# D-Sub_Adapter.net
KiCad netlist of a schematic drawn in EAGLE
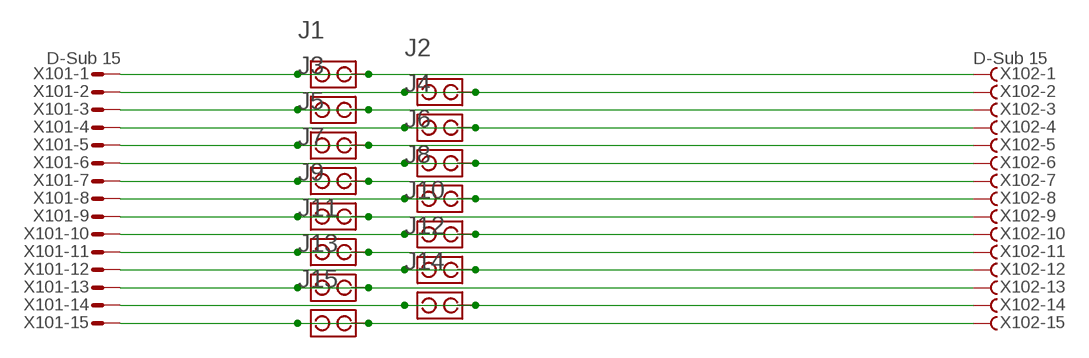
[diagram p0: schematic, sheet 1]

(export (version "E")
  (design (tool "Eeschema 10.0.6"))
  (components
    (comp (ref "J1")
      (value "JUMPER")
      (footprint "eagle-import:JUMPER")
      (libsource (lib "eagle-import") (part "JUMPER"))
    )
    (comp (ref "J2")
      (value "JUMPER")
      (footprint "eagle-import:JUMPER")
      (libsource (lib "eagle-import") (part "JUMPER"))
    )
    (comp (ref "J3")
      (value "JUMPER")
      (footprint "eagle-import:JUMPER")
      (libsource (lib "eagle-import") (part "JUMPER"))
    )
    (comp (ref "J4")
      (value "JUMPER")
      (footprint "eagle-import:JUMPER")
      (libsource (lib "eagle-import") (part "JUMPER"))
    )
    (comp (ref "J5")
      (value "JUMPER")
      (footprint "eagle-import:JUMPER")
      (libsource (lib "eagle-import") (part "JUMPER"))
    )
    (comp (ref "J6")
      (value "JUMPER")
      (footprint "eagle-import:JUMPER")
      (libsource (lib "eagle-import") (part "JUMPER"))
    )
    (comp (ref "J7")
      (value "JUMPER")
      (footprint "eagle-import:JUMPER")
      (libsource (lib "eagle-import") (part "JUMPER"))
    )
    (comp (ref "J8")
      (value "JUMPER")
      (footprint "eagle-import:JUMPER")
      (libsource (lib "eagle-import") (part "JUMPER"))
    )
    (comp (ref "J9")
      (value "JUMPER")
      (footprint "eagle-import:JUMPER")
      (libsource (lib "eagle-import") (part "JUMPER"))
    )
    (comp (ref "J10")
      (value "JUMPER")
      (footprint "eagle-import:JUMPER")
      (libsource (lib "eagle-import") (part "JUMPER"))
    )
    (comp (ref "J11")
      (value "JUMPER")
      (footprint "eagle-import:JUMPER")
      (libsource (lib "eagle-import") (part "JUMPER"))
    )
    (comp (ref "J12")
      (value "JUMPER")
      (footprint "eagle-import:JUMPER")
      (libsource (lib "eagle-import") (part "JUMPER"))
    )
    (comp (ref "J13")
      (value "JUMPER")
      (footprint "eagle-import:JUMPER")
      (libsource (lib "eagle-import") (part "JUMPER"))
    )
    (comp (ref "J14")
      (value "JUMPER")
      (footprint "eagle-import:JUMPER")
      (libsource (lib "eagle-import") (part "JUMPER"))
    )
    (comp (ref "J15")
      (value "JUMPER")
      (footprint "eagle-import:JUMPER")
      (libsource (lib "eagle-import") (part "JUMPER"))
    )
    (comp (ref "X101")
      (value "D-Sub 15")
      (footprint "eagle-import:M15HP")
      (libsource (lib "eagle-import") (part "M15?SHP"))
    )
    (comp (ref "X102")
      (value "D-Sub 15")
      (footprint "eagle-import:F15HP")
      (libsource (lib "eagle-import") (part "F15?SHP"))
    )
  )
  (nets
    (net (code "1") (name "Net-(X101A-M)") (class "Default")
      (node (ref "J1") (pin "1") (pinfunction "1_1") (pintype "bidirectional"))
      (node (ref "J1") (pin "2") (pinfunction "2_2") (pintype "bidirectional"))
      (node (ref "X101") (pin "1") (pinfunction "M_1") (pintype "passive"))
      (node (ref "X102") (pin "1") (pinfunction "F_1") (pintype "passive"))
    )
    (net (code "2") (name "Net-(X101B-M)") (class "Default")
      (node (ref "J10") (pin "1") (pinfunction "1_1") (pintype "bidirectional"))
      (node (ref "J10") (pin "2") (pinfunction "2_2") (pintype "bidirectional"))
      (node (ref "X101") (pin "10") (pinfunction "M_10") (pintype "passive"))
      (node (ref "X102") (pin "10") (pinfunction "F_10") (pintype "passive"))
    )
    (net (code "3") (name "Net-(X101C-M)") (class "Default")
      (node (ref "J11") (pin "1") (pinfunction "1_1") (pintype "bidirectional"))
      (node (ref "J11") (pin "2") (pinfunction "2_2") (pintype "bidirectional"))
      (node (ref "X101") (pin "11") (pinfunction "M_11") (pintype "passive"))
      (node (ref "X102") (pin "11") (pinfunction "F_11") (pintype "passive"))
    )
    (net (code "4") (name "Net-(X101D-M)") (class "Default")
      (node (ref "J12") (pin "1") (pinfunction "1_1") (pintype "bidirectional"))
      (node (ref "J12") (pin "2") (pinfunction "2_2") (pintype "bidirectional"))
      (node (ref "X101") (pin "12") (pinfunction "M_12") (pintype "passive"))
      (node (ref "X102") (pin "12") (pinfunction "F_12") (pintype "passive"))
    )
    (net (code "5") (name "Net-(X101E-M)") (class "Default")
      (node (ref "J13") (pin "1") (pinfunction "1_1") (pintype "bidirectional"))
      (node (ref "J13") (pin "2") (pinfunction "2_2") (pintype "bidirectional"))
      (node (ref "X101") (pin "13") (pinfunction "M_13") (pintype "passive"))
      (node (ref "X102") (pin "13") (pinfunction "F_13") (pintype "passive"))
    )
    (net (code "6") (name "Net-(X101F-M)") (class "Default")
      (node (ref "J14") (pin "1") (pinfunction "1_1") (pintype "bidirectional"))
      (node (ref "J14") (pin "2") (pinfunction "2_2") (pintype "bidirectional"))
      (node (ref "X101") (pin "14") (pinfunction "M_14") (pintype "passive"))
      (node (ref "X102") (pin "14") (pinfunction "F_14") (pintype "passive"))
    )
    (net (code "7") (name "Net-(X101G-M)") (class "Default")
      (node (ref "J15") (pin "1") (pinfunction "1_1") (pintype "bidirectional"))
      (node (ref "J15") (pin "2") (pinfunction "2_2") (pintype "bidirectional"))
      (node (ref "X101") (pin "15") (pinfunction "M_15") (pintype "passive"))
      (node (ref "X102") (pin "15") (pinfunction "F_15") (pintype "passive"))
    )
    (net (code "8") (name "Net-(X101H-M)") (class "Default")
      (node (ref "J2") (pin "1") (pinfunction "1_1") (pintype "bidirectional"))
      (node (ref "J2") (pin "2") (pinfunction "2_2") (pintype "bidirectional"))
      (node (ref "X101") (pin "2") (pinfunction "M_2") (pintype "passive"))
      (node (ref "X102") (pin "2") (pinfunction "F_2") (pintype "passive"))
    )
    (net (code "9") (name "Net-(X101I-M)") (class "Default")
      (node (ref "J3") (pin "1") (pinfunction "1_1") (pintype "bidirectional"))
      (node (ref "J3") (pin "2") (pinfunction "2_2") (pintype "bidirectional"))
      (node (ref "X101") (pin "3") (pinfunction "M_3") (pintype "passive"))
      (node (ref "X102") (pin "3") (pinfunction "F_3") (pintype "passive"))
    )
    (net (code "10") (name "Net-(X101J-M)") (class "Default")
      (node (ref "J4") (pin "1") (pinfunction "1_1") (pintype "bidirectional"))
      (node (ref "J4") (pin "2") (pinfunction "2_2") (pintype "bidirectional"))
      (node (ref "X101") (pin "4") (pinfunction "M_4") (pintype "passive"))
      (node (ref "X102") (pin "4") (pinfunction "F_4") (pintype "passive"))
    )
    (net (code "11") (name "Net-(X101K-M)") (class "Default")
      (node (ref "J5") (pin "1") (pinfunction "1_1") (pintype "bidirectional"))
      (node (ref "J5") (pin "2") (pinfunction "2_2") (pintype "bidirectional"))
      (node (ref "X101") (pin "5") (pinfunction "M_5") (pintype "passive"))
      (node (ref "X102") (pin "5") (pinfunction "F_5") (pintype "passive"))
    )
    (net (code "12") (name "Net-(X101L-M)") (class "Default")
      (node (ref "J6") (pin "1") (pinfunction "1_1") (pintype "bidirectional"))
      (node (ref "J6") (pin "2") (pinfunction "2_2") (pintype "bidirectional"))
      (node (ref "X101") (pin "6") (pinfunction "M_6") (pintype "passive"))
      (node (ref "X102") (pin "6") (pinfunction "F_6") (pintype "passive"))
    )
    (net (code "13") (name "Net-(X101M-M)") (class "Default")
      (node (ref "J7") (pin "1") (pinfunction "1_1") (pintype "bidirectional"))
      (node (ref "J7") (pin "2") (pinfunction "2_2") (pintype "bidirectional"))
      (node (ref "X101") (pin "7") (pinfunction "M_7") (pintype "passive"))
      (node (ref "X102") (pin "7") (pinfunction "F_7") (pintype "passive"))
    )
    (net (code "14") (name "Net-(X101N-M)") (class "Default")
      (node (ref "J8") (pin "1") (pinfunction "1_1") (pintype "bidirectional"))
      (node (ref "J8") (pin "2") (pinfunction "2_2") (pintype "bidirectional"))
      (node (ref "X101") (pin "8") (pinfunction "M_8") (pintype "passive"))
      (node (ref "X102") (pin "8") (pinfunction "F_8") (pintype "passive"))
    )
    (net (code "15") (name "Net-(X101O-M)") (class "Default")
      (node (ref "J9") (pin "1") (pinfunction "1_1") (pintype "bidirectional"))
      (node (ref "J9") (pin "2") (pinfunction "2_2") (pintype "bidirectional"))
      (node (ref "X101") (pin "9") (pinfunction "M_9") (pintype "passive"))
      (node (ref "X102") (pin "9") (pinfunction "F_9") (pintype "passive"))
    )
  )
)
